# Communication.net
KiCad netlist of a schematic drawn in Altium Designer
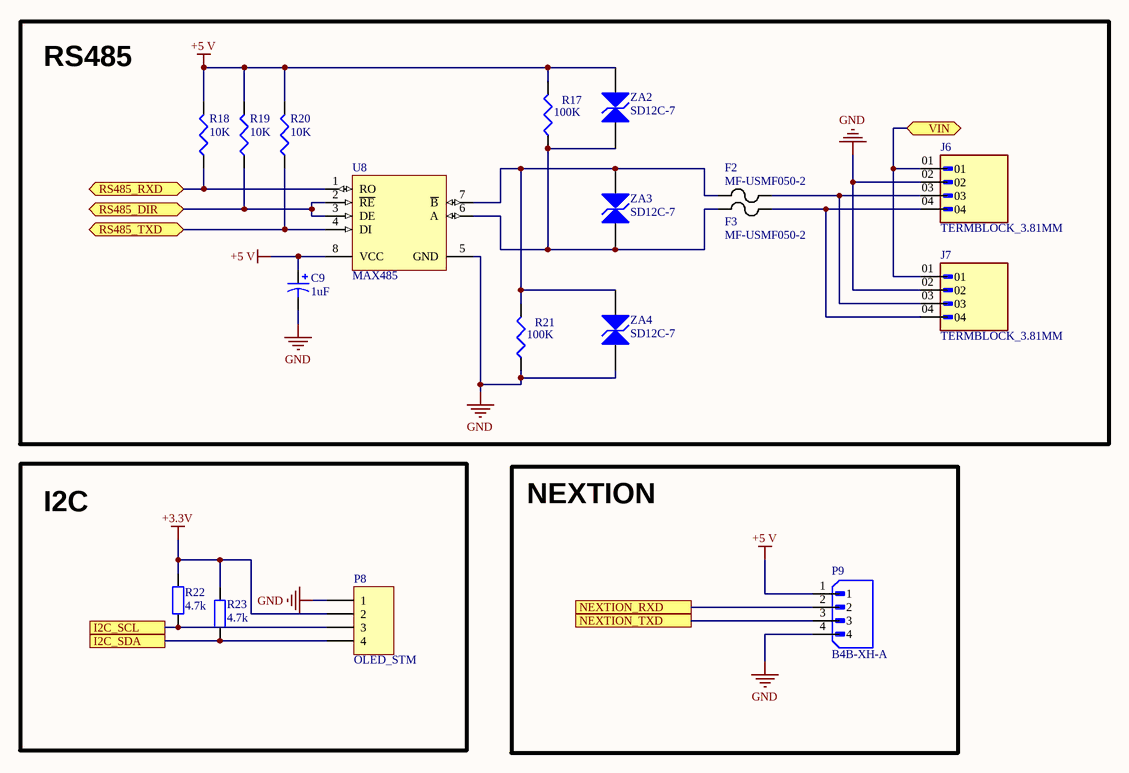
[diagram p0: Communication.SchDoc]

(export (version "E")
  (design (tool "Eeschema 10.0.6"))
  (components
    (comp (ref "C9")
      (value "1uF")
      (footprint "CAPC3225N")
      (description "Polarized Capacitor (Surface Mount)")
      (fields (field (name "PUBLISHER") "Altium Limited"))
      (libsource (lib "Miscellaneous Devices") (part "Cap Pol3"))
    )
    (comp (ref "F2")
      (value "MF-USMF050-2")
      (footprint "MF-USMF050-2")
      (description "PTC RESET FUSE 6V 3A 1812")
      (libsource (lib "Adox_Lib") (part "PTS18126V300"))
    )
    (comp (ref "F3")
      (value "MF-USMF050-2")
      (footprint "MF-USMF050-2")
      (description "PTC RESET FUSE 6V 3A 1812")
      (libsource (lib "Adox_Lib") (part "PTS18126V300"))
    )
    (comp (ref "J6")
      (value "TERMBLOCK_3.81MM")
      (footprint "TERMBLOCK_3.81MM_90DEG_4POS")
      (description "TERMBLOCK_3.81MM_90DEG_4POS (DigiKey: 1803293)")
      (libsource (lib "MH_Lib") (part "TERMBLOCK_3.81MM_90DEG_4POS"))
    )
    (comp (ref "J7")
      (value "TERMBLOCK_3.81MM")
      (footprint "TERMBLOCK_3.81MM_90DEG_4POS")
      (description "TERMBLOCK_3.81MM_90DEG_4POS (DigiKey: 1803293)")
      (libsource (lib "MH_Lib") (part "TERMBLOCK_3.81MM_90DEG_4POS"))
    )
    (comp (ref "P8")
      (value "OLED_STM")
      (footprint "CONNHDR_1X4_2.54MM")
      (description "Header, 4-Pin")
      (fields (field (name "PUBLISHER") "Altium Limited"))
      (libsource (lib "Miscellaneous Connectors") (part "MHDR1X4"))
    )
    (comp (ref "P9")
      (value "B4B-XH-A")
      (footprint "CONN-B4B-XH-A")
      (description "CONN HEADER VERT 4POS 2.5MM")
      (libsource (lib "MH_Lib") (part "CONN-B4B-XH-A"))
    )
    (comp (ref "R17")
      (value "100K")
      (footprint "RESC2012N")
      (description "Resistor")
      (fields (field (name "PUBLISHER") "Altium Limited"))
      (libsource (lib "Miscellaneous Devices") (part "Res3"))
    )
    (comp (ref "R18")
      (value "10K")
      (footprint "RESC2012N")
      (description "Resistor")
      (fields (field (name "PUBLISHER") "Altium Limited"))
      (libsource (lib "Miscellaneous Devices") (part "Res3"))
    )
    (comp (ref "R19")
      (value "10K")
      (footprint "RESC2012N")
      (description "Resistor")
      (fields (field (name "PUBLISHER") "Altium Limited"))
      (libsource (lib "Miscellaneous Devices") (part "Res3"))
    )
    (comp (ref "R20")
      (value "10K")
      (footprint "RESC2012N")
      (description "Resistor")
      (fields (field (name "PUBLISHER") "Altium Limited"))
      (libsource (lib "Miscellaneous Devices") (part "Res3"))
    )
    (comp (ref "R21")
      (value "100K")
      (footprint "RESC2012N")
      (description "Resistor")
      (fields (field (name "PUBLISHER") "Altium Limited"))
      (libsource (lib "Miscellaneous Devices") (part "Res3"))
    )
    (comp (ref "R22")
      (value "4.7k")
      (footprint "RESC2012N")
      (description "Resistor")
      (fields (field (name "PUBLISHER") "Altium Limited"))
      (libsource (lib "Miscellaneous Devices") (part "Res2"))
    )
    (comp (ref "R23")
      (value "4.7k")
      (footprint "RESC2012N")
      (description "Resistor")
      (fields (field (name "PUBLISHER") "Altium Limited"))
      (libsource (lib "Miscellaneous Devices") (part "Res2"))
    )
    (comp (ref "U8")
      (value "MAX485")
      (footprint "MAX485")
      (description "Low-Power RS-485/RS-422 Multipoint Transceiver, 8-pin Narrow SOIC")
      (libsource (lib "MH_Lib") (part "MAX485"))
    )
    (comp (ref "ZA2")
      (value "SD12C-7")
      (footprint "SOD-323")
      (description "Transient voltage suppressor diode")
      (libsource (lib "Adox_Lib") (part "TVS Diode"))
    )
    (comp (ref "ZA3")
      (value "SD12C-7")
      (footprint "SOD-323")
      (description "Transient voltage suppressor diode")
      (libsource (lib "Adox_Lib") (part "TVS Diode"))
    )
    (comp (ref "ZA4")
      (value "SD12C-7")
      (footprint "SOD-323")
      (description "Transient voltage suppressor diode")
      (libsource (lib "Adox_Lib") (part "TVS Diode"))
    )
  )
  (nets
    (net (code "1") (name "+3.3V") (class "Default")
      (node (ref "P8") (pin "2") (pinfunction "2_2") (pintype "passive"))
      (node (ref "R22") (pin "2") (pinfunction "2_2") (pintype "passive"))
      (node (ref "R23") (pin "2") (pinfunction "2_2") (pintype "passive"))
    )
    (net (code "2") (name "+5 V") (class "Default")
      (node (ref "C9") (pin "1") (pinfunction "1_1") (pintype "passive"))
      (node (ref "P9") (pin "1") (pinfunction "1_1") (pintype "passive"))
      (node (ref "R17") (pin "2") (pinfunction "2_2") (pintype "passive"))
      (node (ref "R18") (pin "2") (pinfunction "2_2") (pintype "passive"))
      (node (ref "R19") (pin "2") (pinfunction "2_2") (pintype "passive"))
      (node (ref "R20") (pin "2") (pinfunction "2_2") (pintype "passive"))
      (node (ref "U8") (pin "8") (pinfunction "VCC_8") (pintype "power_in"))
      (node (ref "ZA2") (pin "1") (pinfunction "1_1") (pintype "passive"))
    )
    (net (code "3") (name "/I2C_SCL") (class "Default")
      (node (ref "P8") (pin "3") (pinfunction "3_3") (pintype "passive"))
      (node (ref "R22") (pin "1") (pinfunction "1_1") (pintype "passive"))
    )
    (net (code "4") (name "/I2C_SDA") (class "Default")
      (node (ref "P8") (pin "4") (pinfunction "4_4") (pintype "passive"))
      (node (ref "R23") (pin "1") (pinfunction "1_1") (pintype "passive"))
    )
    (net (code "5") (name "/NEXTION_RXD") (class "Default")
      (node (ref "P9") (pin "2") (pinfunction "2_2") (pintype "passive"))
    )
    (net (code "6") (name "/NEXTION_TXD") (class "Default")
      (node (ref "P9") (pin "3") (pinfunction "3_3") (pintype "passive"))
    )
    (net (code "7") (name "/RS485_DIR") (class "Default")
      (node (ref "R19") (pin "1") (pinfunction "1_1") (pintype "passive"))
      (node (ref "U8") (pin "2") (pinfunction "~{RE}_2") (pintype "input"))
      (node (ref "U8") (pin "3") (pinfunction "DE_3") (pintype "input"))
    )
    (net (code "8") (name "/RS485_RXD") (class "Default")
      (node (ref "R18") (pin "1") (pinfunction "1_1") (pintype "passive"))
      (node (ref "U8") (pin "1") (pinfunction "RO_1") (pintype "bidirectional"))
    )
    (net (code "9") (name "/RS485_TXD") (class "Default")
      (node (ref "R20") (pin "1") (pinfunction "1_1") (pintype "passive"))
      (node (ref "U8") (pin "4") (pinfunction "DI_4") (pintype "input"))
    )
    (net (code "10") (name "/VIN") (class "Default")
      (node (ref "J6") (pin "01") (pinfunction "01_01") (pintype "passive"))
      (node (ref "J7") (pin "01") (pinfunction "01_01") (pintype "passive"))
    )
    (net (code "11") (name "GND") (class "Default")
      (node (ref "C9") (pin "2") (pinfunction "2_2") (pintype "passive"))
      (node (ref "J6") (pin "02") (pinfunction "02_02") (pintype "passive"))
      (node (ref "J7") (pin "02") (pinfunction "02_02") (pintype "passive"))
      (node (ref "P8") (pin "1") (pinfunction "1_1") (pintype "passive"))
      (node (ref "P9") (pin "4") (pinfunction "4_4") (pintype "passive"))
      (node (ref "R21") (pin "1") (pinfunction "1_1") (pintype "passive"))
      (node (ref "U8") (pin "5") (pinfunction "GND_5") (pintype "power_in"))
      (node (ref "ZA4") (pin "2") (pinfunction "2_2") (pintype "passive"))
    )
    (net (code "12") (name "Net-(F2-Pad2)") (class "Default")
      (node (ref "F2") (pin "2") (pinfunction "2_2") (pintype "passive"))
      (node (ref "J6") (pin "03") (pinfunction "03_03") (pintype "passive"))
      (node (ref "J7") (pin "03") (pinfunction "03_03") (pintype "passive"))
    )
    (net (code "13") (name "Net-(F3-Pad2)") (class "Default")
      (node (ref "F3") (pin "2") (pinfunction "2_2") (pintype "passive"))
      (node (ref "J6") (pin "04") (pinfunction "04_04") (pintype "passive"))
      (node (ref "J7") (pin "04") (pinfunction "04_04") (pintype "passive"))
    )
    (net (code "14") (name "Net-(U8-A)") (class "Default")
      (node (ref "F3") (pin "1") (pinfunction "1_1") (pintype "passive"))
      (node (ref "R17") (pin "1") (pinfunction "1_1") (pintype "passive"))
      (node (ref "U8") (pin "6") (pinfunction "A_6") (pintype "bidirectional"))
      (node (ref "ZA2") (pin "2") (pinfunction "2_2") (pintype "passive"))
      (node (ref "ZA3") (pin "2") (pinfunction "2_2") (pintype "passive"))
    )
    (net (code "15") (name "Net-(U8-~{B})") (class "Default")
      (node (ref "F2") (pin "1") (pinfunction "1_1") (pintype "passive"))
      (node (ref "R21") (pin "2") (pinfunction "2_2") (pintype "passive"))
      (node (ref "U8") (pin "7") (pinfunction "~{B}_7") (pintype "bidirectional"))
      (node (ref "ZA3") (pin "1") (pinfunction "1_1") (pintype "passive"))
      (node (ref "ZA4") (pin "1") (pinfunction "1_1") (pintype "passive"))
    )
  )
)
